# Charging_Cap_1p25kV.net
KiCad netlist of a schematic drawn in Altium Designer
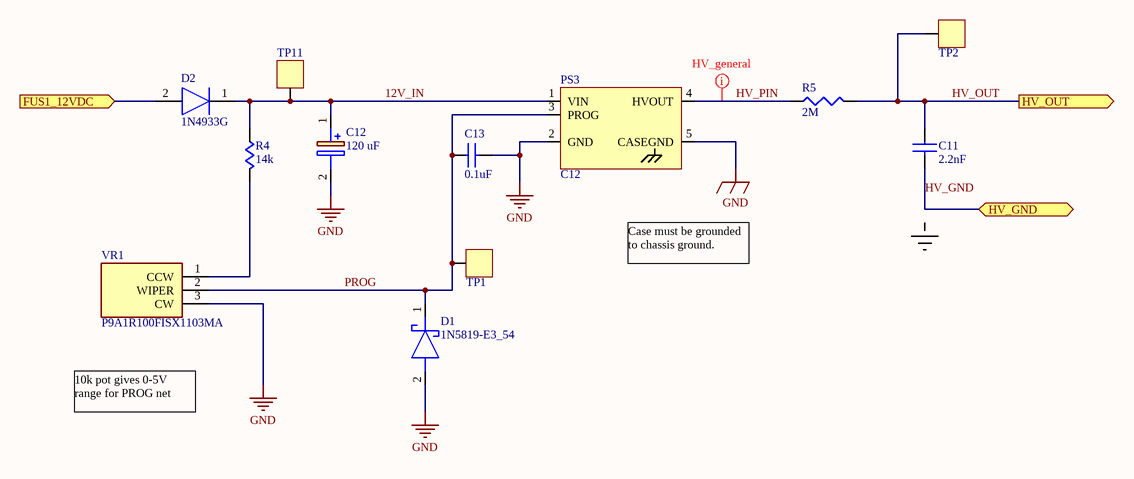
[diagram p0: Charging_Cap_1p25kV.SchDoc]

(export (version "E")
  (design (tool "Eeschema 10.0.6"))
  (components
    (comp (ref "C11")
      (value "2.2nF")
      (footprint "C331C222KHR5HA")
      (description "Multilayer Ceramic Capacitors MLCC - Leaded 3000V 2200pF X7R 10% LS=6.35mm")
      (libsource (lib "pulser_driver_symbols") (part "C331C222KHR5HA"))
    )
    (comp (ref "C12")
      (value "120 uF")
      (footprint "CAPPRD500W65D1000H1400")
      (description "Capacitor Polarised")
      (fields (field (name "MANUFACTURER_PART_NUMBER") "EEU-TP1V121"))
      (libsource (lib "pulser_driver_symbols") (part "EEU-TP1V121"))
    )
    (comp (ref "C13")
      (value "0.1uF")
      (footprint "C420C104K5R5TA7200")
      (description "CAP CER TH 0.1UF 50V X7R AXIAL")
      (libsource (lib "pulser_driver_symbols") (part "C420C104K5R5TA7200"))
    )
    (comp (ref "D1")
      (value "1N5819-E3_54")
      (footprint "DIOAD1405W86L465D235")
      (description "Schottky Diode")
      (fields
        (field (name "MANUFACTURER_PART_NUMBER") "1N5819-E3/54")
        (field (name "MOUSER PART NUMBER") "625-1N5819-E3")
      )
      (libsource (lib "pulser_driver_symbols") (part "1N5819-E3_54"))
    )
    (comp (ref "D2")
      (value "1N4933G")
      (footprint "DIOAD1405W86L465D235")
      (description "Rectifiers 50V 1A Fast")
      (fields (field (name "MOUSER PART NUMBER") "863-1N4933G"))
      (libsource (lib "pulser_driver_symbols") (part "1N4933G"))
    )
    (comp (ref "PS3")
      (value "C12")
      (footprint "C12")
      (description "MPN is C12, DC DC conv")
      (libsource (lib "pulser_driver_symbols") (part "C12"))
    )
    (comp (ref "R4")
      (value "14k")
      (footprint "MFR-25FBF52-14K")
      (description "RES TH 14K OHM 1% 1/4W AXIAL")
      (libsource (lib "pulser_driver_symbols") (part "MFR-25FBF52-14K"))
    )
    (comp (ref "R5")
      (value "2M")
      (footprint "HHV1WSJT-73-2M")
      (description "RES 2M OHM 5% 1W AXIAL")
      (libsource (lib "pulser_driver_symbols") (part "HHV1WSJT-73-2M"))
    )
    (comp (ref "TP1")
      (value "5261")
      (footprint "5261")
      (description "TEST POINT grabber (BLACK) - MINIATURE")
      (libsource (lib "") (part "5261_1"))
    )
    (comp (ref "TP2")
      (value "5261")
      (footprint "5261")
      (description "TEST POINT grabber (BLACK) - MINIATURE")
      (libsource (lib "") (part "5261_1"))
    )
    (comp (ref "TP11")
      (value "5261")
      (footprint "5261")
      (description "TEST POINT grabber (BLACK) - MINIATURE")
      (libsource (lib "pulser_driver_symbols") (part "5261"))
    )
    (comp (ref "VR1")
      (value "P9A1R100FISX1103MA")
      (footprint "P9A1R100FISX1103MA")
      (description "Variable Resistor 10K")
      (fields (field (name "MOUSER PART NUMBER") "72-P9A1RFISX1BB2103M"))
      (libsource (lib "pulser_driver_symbols") (part "P9A1R100FISX1103MA"))
    )
  )
  (nets
    (net (code "1") (name "/12V_IN") (class "Default")
      (node (ref "C12") (pin "1") (pinfunction "+_1") (pintype "passive"))
      (node (ref "D2") (pin "1") (pinfunction "K_1") (pintype "passive"))
      (node (ref "PS3") (pin "1") (pinfunction "VIN_1") (pintype "passive"))
      (node (ref "R4") (pin "1") (pinfunction "1_1") (pintype "passive"))
      (node (ref "TP11") (pin "1") (pinfunction "1_1") (pintype "passive"))
    )
    (net (code "2") (name "/FUS1_12VDC") (class "Default")
      (node (ref "D2") (pin "2") (pinfunction "A_2") (pintype "passive"))
    )
    (net (code "3") (name "/HV_GND") (class "Default")
      (node (ref "C11") (pin "2") (pinfunction "2_2") (pintype "passive"))
    )
    (net (code "4") (name "/HV_OUT") (class "Default")
      (node (ref "C11") (pin "1") (pinfunction "1_1") (pintype "passive"))
      (node (ref "R5") (pin "2") (pinfunction "2_2") (pintype "passive"))
      (node (ref "TP2") (pin "1") (pinfunction "1_1") (pintype "passive"))
    )
    (net (code "5") (name "/HV_PIN") (class "Default")
      (node (ref "PS3") (pin "4") (pinfunction "HVOUT_4") (pintype "passive"))
      (node (ref "R5") (pin "1") (pinfunction "1_1") (pintype "passive"))
    )
    (net (code "6") (name "/PROG") (class "Default")
      (node (ref "C13") (pin "1") (pinfunction "1_1") (pintype "passive"))
      (node (ref "D1") (pin "1") (pinfunction "K_1") (pintype "passive"))
      (node (ref "PS3") (pin "3") (pinfunction "PROG_3") (pintype "passive"))
      (node (ref "TP1") (pin "1") (pinfunction "1_1") (pintype "passive"))
      (node (ref "VR1") (pin "2") (pinfunction "WIPER_2") (pintype "passive"))
    )
    (net (code "7") (name "GND") (class "Default")
      (node (ref "C12") (pin "2") (pinfunction "-_2") (pintype "passive"))
      (node (ref "C13") (pin "2") (pinfunction "2_2") (pintype "passive"))
      (node (ref "D1") (pin "2") (pinfunction "A_2") (pintype "passive"))
      (node (ref "PS3") (pin "2") (pinfunction "GND_2") (pintype "passive"))
      (node (ref "PS3") (pin "5") (pinfunction "CASEGND_5") (pintype "passive"))
      (node (ref "VR1") (pin "3") (pinfunction "CW_3") (pintype "passive"))
    )
    (net (code "8") (name "Net-(VR1-CCW)") (class "Default")
      (node (ref "R4") (pin "2") (pinfunction "2_2") (pintype "passive"))
      (node (ref "VR1") (pin "1") (pinfunction "CCW_1") (pintype "passive"))
    )
  )
)
